# Nusbio_2_-_IC2_Extension.net
KiCad netlist of a schematic drawn in EAGLE
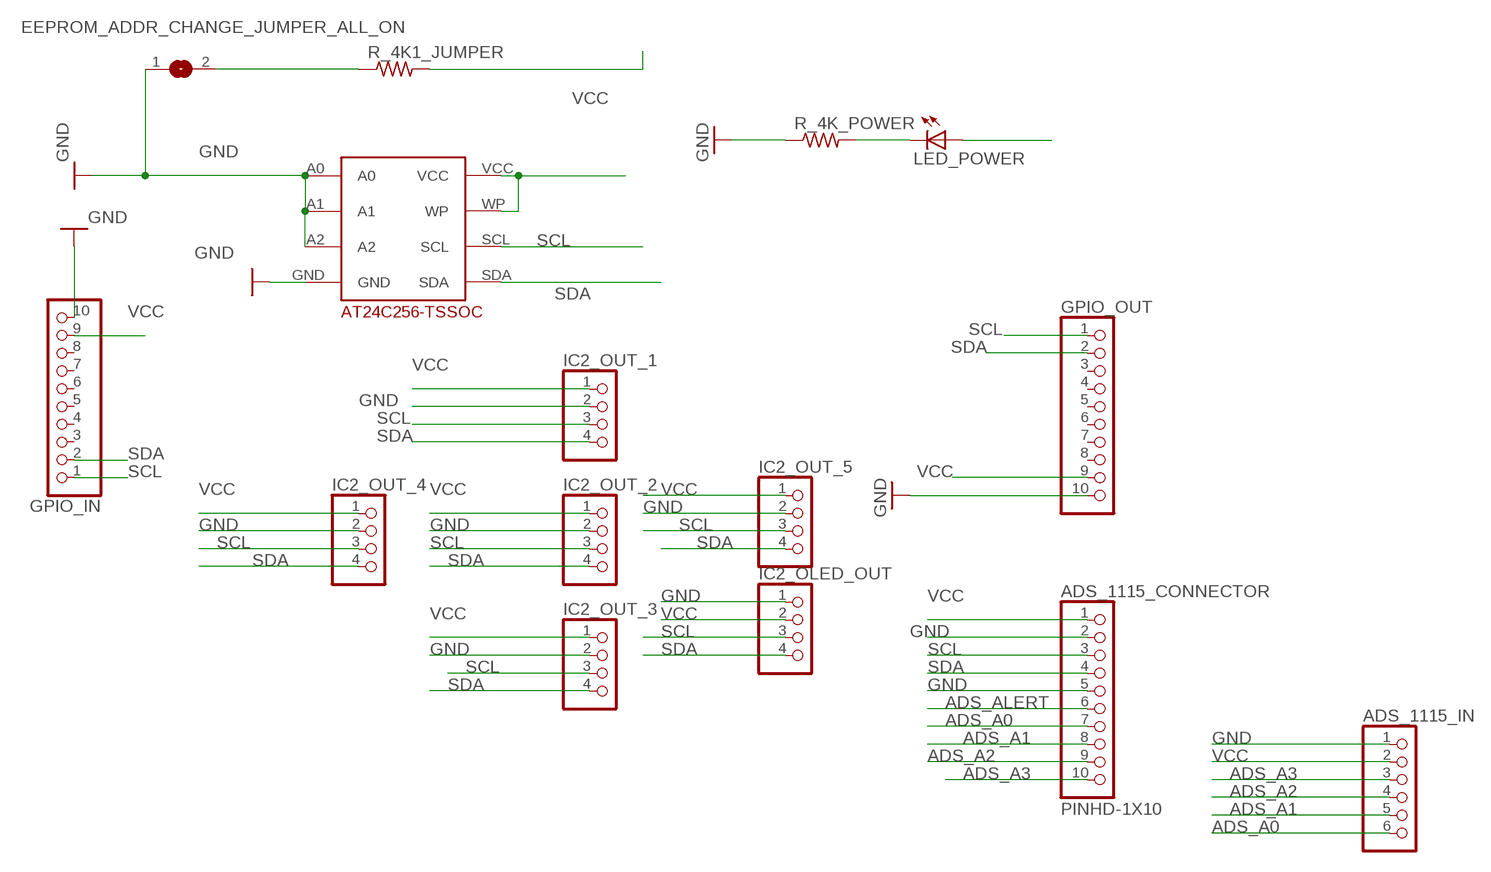
[diagram p0: schematic, sheet 1]

(export (version "E")
  (design (tool "Eeschema 10.0.6"))
  (components
    (comp (ref "ADS_1115_CONNECTOR")
      (value "PINHD-1X10")
      (footprint "eagle-import:1X10-BIG")
      (libsource (lib "eagle-import") (part "PINHD-1X10"))
    )
    (comp (ref "ADS_1115_IN")
      (value "PINHD-1X6")
      (footprint "eagle-import:1X06")
      (libsource (lib "eagle-import") (part "PINHD-1X6"))
    )
    (comp (ref "EEPROM_ADDR_CHANGE_JUMPER_ALL_ON")
      (value "SOLDERJUMPERREFLOW")
      (footprint "eagle-import:SOLDERJUMPER_REFLOW")
      (libsource (lib "eagle-import") (part "SOLDERJUMPERREFLOW"))
    )
    (comp (ref "EEPROM_AT24C256")
      (value "DECADE-AT24C256-10TI-2.7")
      (footprint "eagle-import:DECADE-AT24CXX")
      (libsource (lib "eagle-import") (part "DECADE-AT24C256-10TI-2.7"))
    )
    (comp (ref "GPIO_IN")
      (value "PINHD-1X10")
      (footprint "eagle-import:1X10-BIG")
      (libsource (lib "eagle-import") (part "PINHD-1X10"))
    )
    (comp (ref "GPIO_OUT")
      (value "PINHD-1X10")
      (footprint "eagle-import:1X10-BIG")
      (libsource (lib "eagle-import") (part "PINHD-1X10"))
    )
    (comp (ref "IC2_OLED_OUT")
      (value "PINHD-1X4")
      (footprint "eagle-import:1X04")
      (libsource (lib "eagle-import") (part "PINHD-1X4"))
    )
    (comp (ref "IC2_OUT_1")
      (value "PINHD-1X4")
      (footprint "eagle-import:1X04")
      (libsource (lib "eagle-import") (part "PINHD-1X4"))
    )
    (comp (ref "IC2_OUT_2")
      (value "PINHD-1X4")
      (footprint "eagle-import:1X04")
      (libsource (lib "eagle-import") (part "PINHD-1X4"))
    )
    (comp (ref "IC2_OUT_3")
      (value "PINHD-1X4")
      (footprint "eagle-import:1X04")
      (libsource (lib "eagle-import") (part "PINHD-1X4"))
    )
    (comp (ref "IC2_OUT_4")
      (value "PINHD-1X4")
      (footprint "eagle-import:1X04")
      (libsource (lib "eagle-import") (part "PINHD-1X4"))
    )
    (comp (ref "IC2_OUT_5")
      (value "PINHD-1X4")
      (footprint "eagle-import:1X04")
      (libsource (lib "eagle-import") (part "PINHD-1X4"))
    )
    (comp (ref "LED_POWER")
      (value "LEDSMT1206")
      (footprint "eagle-import:1206")
      (libsource (lib "eagle-import") (part "LEDSMT1206"))
    )
    (comp (ref "R_4K1_JUMPER")
      (value "R-US_R1206")
      (footprint "eagle-import:R1206")
      (libsource (lib "eagle-import") (part "R-US_R1206"))
    )
    (comp (ref "R_4K_POWER")
      (value "R-US_R1206")
      (footprint "eagle-import:R1206")
      (libsource (lib "eagle-import") (part "R-US_R1206"))
    )
  )
  (nets
    (net (code "1") (name "/ADS_A0") (class "Default")
      (node (ref "ADS_1115_CONNECTOR") (pin "7") (pinfunction "7_7") (pintype "passive"))
      (node (ref "ADS_1115_IN") (pin "6") (pinfunction "6_6") (pintype "passive"))
    )
    (net (code "2") (name "/ADS_A1") (class "Default")
      (node (ref "ADS_1115_CONNECTOR") (pin "8") (pinfunction "8_8") (pintype "passive"))
      (node (ref "ADS_1115_IN") (pin "5") (pinfunction "5_5") (pintype "passive"))
    )
    (net (code "3") (name "/ADS_A2") (class "Default")
      (node (ref "ADS_1115_CONNECTOR") (pin "9") (pinfunction "9_9") (pintype "passive"))
      (node (ref "ADS_1115_IN") (pin "4") (pinfunction "4_4") (pintype "passive"))
    )
    (net (code "4") (name "/ADS_A3") (class "Default")
      (node (ref "ADS_1115_CONNECTOR") (pin "10") (pinfunction "10_10") (pintype "passive"))
      (node (ref "ADS_1115_IN") (pin "3") (pinfunction "3_3") (pintype "passive"))
    )
    (net (code "5") (name "/ADS_ALERT") (class "Default")
      (node (ref "ADS_1115_CONNECTOR") (pin "6") (pinfunction "6_6") (pintype "passive"))
    )
    (net (code "6") (name "/SCL") (class "Default")
      (node (ref "ADS_1115_CONNECTOR") (pin "3") (pinfunction "3_3") (pintype "passive"))
      (node (ref "EEPROM_AT24C256") (pin "SCL") (pinfunction "SCL_SCL") (pintype "bidirectional"))
      (node (ref "GPIO_IN") (pin "1") (pinfunction "1_1") (pintype "passive"))
      (node (ref "GPIO_OUT") (pin "1") (pinfunction "1_1") (pintype "passive"))
      (node (ref "IC2_OLED_OUT") (pin "3") (pinfunction "3_3") (pintype "passive"))
      (node (ref "IC2_OUT_1") (pin "3") (pinfunction "3_3") (pintype "passive"))
      (node (ref "IC2_OUT_2") (pin "3") (pinfunction "3_3") (pintype "passive"))
      (node (ref "IC2_OUT_3") (pin "3") (pinfunction "3_3") (pintype "passive"))
      (node (ref "IC2_OUT_4") (pin "3") (pinfunction "3_3") (pintype "passive"))
      (node (ref "IC2_OUT_5") (pin "3") (pinfunction "3_3") (pintype "passive"))
    )
    (net (code "7") (name "/SDA") (class "Default")
      (node (ref "ADS_1115_CONNECTOR") (pin "4") (pinfunction "4_4") (pintype "passive"))
      (node (ref "EEPROM_AT24C256") (pin "SDA") (pinfunction "SDA_SDA") (pintype "bidirectional"))
      (node (ref "GPIO_IN") (pin "2") (pinfunction "2_2") (pintype "passive"))
      (node (ref "GPIO_OUT") (pin "2") (pinfunction "2_2") (pintype "passive"))
      (node (ref "IC2_OLED_OUT") (pin "4") (pinfunction "4_4") (pintype "passive"))
      (node (ref "IC2_OUT_1") (pin "4") (pinfunction "4_4") (pintype "passive"))
      (node (ref "IC2_OUT_2") (pin "4") (pinfunction "4_4") (pintype "passive"))
      (node (ref "IC2_OUT_3") (pin "4") (pinfunction "4_4") (pintype "passive"))
      (node (ref "IC2_OUT_4") (pin "4") (pinfunction "4_4") (pintype "passive"))
      (node (ref "IC2_OUT_5") (pin "4") (pinfunction "4_4") (pintype "passive"))
    )
    (net (code "8") (name "/VCC") (class "Default")
      (node (ref "ADS_1115_CONNECTOR") (pin "1") (pinfunction "1_1") (pintype "passive"))
      (node (ref "ADS_1115_IN") (pin "2") (pinfunction "2_2") (pintype "passive"))
      (node (ref "GPIO_IN") (pin "9") (pinfunction "9_9") (pintype "passive"))
      (node (ref "GPIO_OUT") (pin "9") (pinfunction "9_9") (pintype "passive"))
      (node (ref "IC2_OLED_OUT") (pin "2") (pinfunction "2_2") (pintype "passive"))
      (node (ref "IC2_OUT_1") (pin "1") (pinfunction "1_1") (pintype "passive"))
      (node (ref "IC2_OUT_2") (pin "1") (pinfunction "1_1") (pintype "passive"))
      (node (ref "IC2_OUT_3") (pin "1") (pinfunction "1_1") (pintype "passive"))
      (node (ref "IC2_OUT_4") (pin "1") (pinfunction "1_1") (pintype "passive"))
      (node (ref "IC2_OUT_5") (pin "1") (pinfunction "1_1") (pintype "passive"))
      (node (ref "LED_POWER") (pin "A") (pinfunction "A_A") (pintype "passive"))
      (node (ref "R_4K1_JUMPER") (pin "2") (pinfunction "2_2") (pintype "passive"))
    )
    (net (code "9") (name "GND") (class "Default")
      (node (ref "ADS_1115_CONNECTOR") (pin "2") (pinfunction "2_2") (pintype "passive"))
      (node (ref "ADS_1115_CONNECTOR") (pin "5") (pinfunction "5_5") (pintype "passive"))
      (node (ref "ADS_1115_IN") (pin "1") (pinfunction "1_1") (pintype "passive"))
      (node (ref "EEPROM_ADDR_CHANGE_JUMPER_ALL_ON") (pin "1") (pinfunction "1_1") (pintype "passive"))
      (node (ref "EEPROM_AT24C256") (pin "A0") (pinfunction "A0_A0") (pintype "bidirectional"))
      (node (ref "EEPROM_AT24C256") (pin "A1") (pinfunction "A1_A1") (pintype "bidirectional"))
      (node (ref "EEPROM_AT24C256") (pin "A2") (pinfunction "A2_A2") (pintype "bidirectional"))
      (node (ref "EEPROM_AT24C256") (pin "GND") (pinfunction "GND_GND") (pintype "bidirectional"))
      (node (ref "GPIO_IN") (pin "10") (pinfunction "10_10") (pintype "passive"))
      (node (ref "GPIO_OUT") (pin "10") (pinfunction "10_10") (pintype "passive"))
      (node (ref "IC2_OLED_OUT") (pin "1") (pinfunction "1_1") (pintype "passive"))
      (node (ref "IC2_OUT_1") (pin "2") (pinfunction "2_2") (pintype "passive"))
      (node (ref "IC2_OUT_2") (pin "2") (pinfunction "2_2") (pintype "passive"))
      (node (ref "IC2_OUT_3") (pin "2") (pinfunction "2_2") (pintype "passive"))
      (node (ref "IC2_OUT_4") (pin "2") (pinfunction "2_2") (pintype "passive"))
      (node (ref "IC2_OUT_5") (pin "2") (pinfunction "2_2") (pintype "passive"))
      (node (ref "R_4K_POWER") (pin "1") (pinfunction "1_1") (pintype "passive"))
    )
    (net (code "10") (name "Net-(EEPROM_ADDR_CHANGE_JUMPER_ALL_ON-Pad2)") (class "Default")
      (node (ref "EEPROM_ADDR_CHANGE_JUMPER_ALL_ON") (pin "2") (pinfunction "2_2") (pintype "passive"))
      (node (ref "R_4K1_JUMPER") (pin "1") (pinfunction "1_1") (pintype "passive"))
    )
    (net (code "11") (name "Net-(EEPROM_AT24C256-PadVCC)") (class "Default")
      (node (ref "EEPROM_AT24C256") (pin "VCC") (pinfunction "VCC_VCC") (pintype "bidirectional"))
      (node (ref "EEPROM_AT24C256") (pin "WP") (pinfunction "WP_WP") (pintype "bidirectional"))
    )
    (net (code "12") (name "Net-(LED_POWER-PadC)") (class "Default")
      (node (ref "LED_POWER") (pin "C") (pinfunction "C_C") (pintype "passive"))
      (node (ref "R_4K_POWER") (pin "2") (pinfunction "2_2") (pintype "passive"))
    )
    (net (code "13") (name "unconnected-(GPIO_IN-Pad3)") (class "Default")
      (node (ref "GPIO_IN") (pin "3") (pinfunction "3_3") (pintype "passive"))
    )
    (net (code "14") (name "unconnected-(GPIO_IN-Pad4)") (class "Default")
      (node (ref "GPIO_IN") (pin "4") (pinfunction "4_4") (pintype "passive"))
    )
    (net (code "15") (name "unconnected-(GPIO_IN-Pad5)") (class "Default")
      (node (ref "GPIO_IN") (pin "5") (pinfunction "5_5") (pintype "passive"))
    )
    (net (code "16") (name "unconnected-(GPIO_IN-Pad6)") (class "Default")
      (node (ref "GPIO_IN") (pin "6") (pinfunction "6_6") (pintype "passive"))
    )
    (net (code "17") (name "unconnected-(GPIO_IN-Pad7)") (class "Default")
      (node (ref "GPIO_IN") (pin "7") (pinfunction "7_7") (pintype "passive"))
    )
    (net (code "18") (name "unconnected-(GPIO_IN-Pad8)") (class "Default")
      (node (ref "GPIO_IN") (pin "8") (pinfunction "8_8") (pintype "passive"))
    )
    (net (code "19") (name "unconnected-(GPIO_OUT-Pad3)") (class "Default")
      (node (ref "GPIO_OUT") (pin "3") (pinfunction "3_3") (pintype "passive"))
    )
    (net (code "20") (name "unconnected-(GPIO_OUT-Pad4)") (class "Default")
      (node (ref "GPIO_OUT") (pin "4") (pinfunction "4_4") (pintype "passive"))
    )
    (net (code "21") (name "unconnected-(GPIO_OUT-Pad5)") (class "Default")
      (node (ref "GPIO_OUT") (pin "5") (pinfunction "5_5") (pintype "passive"))
    )
    (net (code "22") (name "unconnected-(GPIO_OUT-Pad6)") (class "Default")
      (node (ref "GPIO_OUT") (pin "6") (pinfunction "6_6") (pintype "passive"))
    )
    (net (code "23") (name "unconnected-(GPIO_OUT-Pad7)") (class "Default")
      (node (ref "GPIO_OUT") (pin "7") (pinfunction "7_7") (pintype "passive"))
    )
    (net (code "24") (name "unconnected-(GPIO_OUT-Pad8)") (class "Default")
      (node (ref "GPIO_OUT") (pin "8") (pinfunction "8_8") (pintype "passive"))
    )
  )
)
